# wristband_ee459.net
KiCad netlist of a schematic drawn in Altium Designer
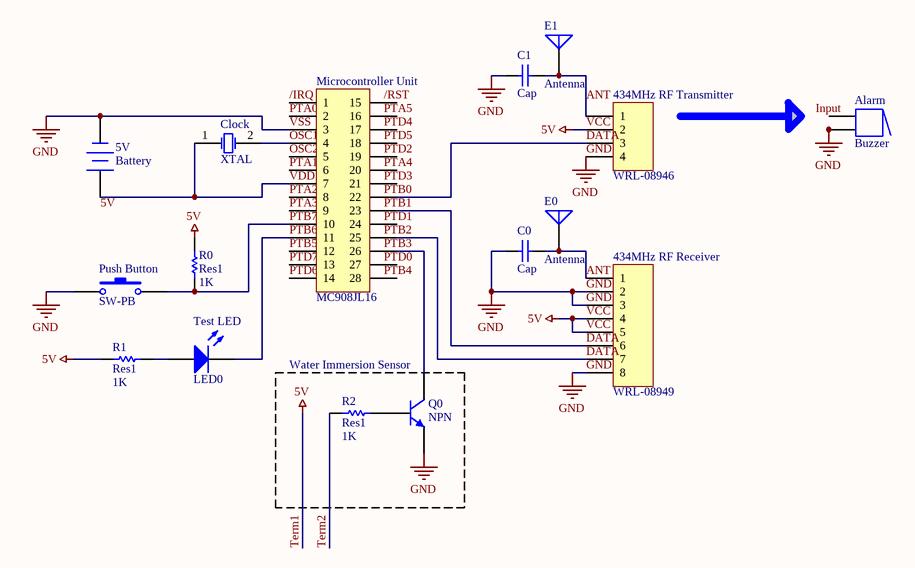
[diagram p0: wristband_ee459.SchDoc]

(export (version "E")
  (design (tool "Eeschema 10.0.6"))
  (components
    (comp (ref "5V")
      (value "Battery")
      (footprint "BAT-2")
      (description "Multicell Battery")
      (fields (field (name "PUBLISHER") "Altium Limited"))
      (libsource (lib "Miscellaneous Devices") (part "Battery"))
    )
    (comp (ref "434MHz RF Receiver")
      (value "WRL-08949")
      (footprint "HDR1X8")
      (description "Header, 8-Pin")
      (fields (field (name "PUBLISHER") "Altium Limited"))
      (libsource (lib "Miscellaneous Connectors") (part "Header 8"))
    )
    (comp (ref "434MHz RF Transmitter")
      (value "WRL-08946")
      (footprint "HDR1X4")
      (description "Header, 4-Pin")
      (fields (field (name "PUBLISHER") "Altium Limited"))
      (libsource (lib "Miscellaneous Connectors") (part "Header 4"))
    )
    (comp (ref "Alarm")
      (value "Buzzer")
      (footprint "ABSM-1574")
      (description "Magnetic Transducer Buzzer")
      (fields (field (name "PUBLISHER") "Altium Limited"))
      (libsource (lib "Miscellaneous Devices") (part "Buzzer"))
    )
    (comp (ref "C0")
      (value "Cap")
      (footprint "RAD-0.3")
      (description "Capacitor")
      (fields (field (name "PUBLISHER") "Altium Limited"))
      (libsource (lib "Miscellaneous Devices") (part "Cap"))
    )
    (comp (ref "C1")
      (value "Cap")
      (footprint "RAD-0.3")
      (description "Capacitor")
      (fields (field (name "PUBLISHER") "Altium Limited"))
      (libsource (lib "Miscellaneous Devices") (part "Cap"))
    )
    (comp (ref "Clock")
      (value "XTAL")
      (footprint "R38")
      (description "Crystal Oscillator")
      (fields (field (name "PUBLISHER") "Altium Limited"))
      (libsource (lib "Miscellaneous Devices") (part "XTAL"))
    )
    (comp (ref "E0")
      (value "Antenna")
      (footprint "PIN1")
      (description "Generic Antenna")
      (fields (field (name "PUBLISHER") "Altium Limited"))
      (libsource (lib "Miscellaneous Devices") (part "Antenna"))
    )
    (comp (ref "E1")
      (value "Antenna")
      (footprint "PIN1")
      (description "Generic Antenna")
      (fields (field (name "PUBLISHER") "Altium Limited"))
      (libsource (lib "Miscellaneous Devices") (part "Antenna"))
    )
    (comp (ref "Microcontroller Unit")
      (value "MC908JL16")
      (footprint "HDR2X14_CEN")
      (description "Header, 14-Pin, Dual row")
      (fields (field (name "PUBLISHER") "Altium Limited"))
      (libsource (lib "Miscellaneous Connectors") (part "Header 14X2A"))
    )
    (comp (ref "Push Button")
      (value "SW-PB")
      (footprint "SPST-2")
      (description "Switch")
      (fields (field (name "PUBLISHER") "Altium Limited"))
      (libsource (lib "Miscellaneous Devices") (part "SW-PB"))
    )
    (comp (ref "Q0")
      (value "NPN")
      (footprint "TO-226")
      (description "NPN Bipolar Transistor")
      (fields (field (name "PUBLISHER") "Altium Limited"))
      (libsource (lib "Miscellaneous Devices") (part "NPN"))
    )
    (comp (ref "R0")
      (value "Res1")
      (footprint "AXIAL-0.3")
      (description "Resistor")
      (fields (field (name "ALTIUM_VALUE") "1K") (field (name "PUBLISHER") "Altium Limited"))
      (libsource (lib "Miscellaneous Devices") (part "Res1"))
    )
    (comp (ref "R1")
      (value "Res1")
      (footprint "AXIAL-0.3")
      (description "Resistor")
      (fields (field (name "ALTIUM_VALUE") "1K") (field (name "PUBLISHER") "Altium Limited"))
      (libsource (lib "Miscellaneous Devices") (part "Res1"))
    )
    (comp (ref "R2")
      (value "Res1")
      (footprint "AXIAL-0.3")
      (description "Resistor")
      (fields (field (name "ALTIUM_VALUE") "1K") (field (name "PUBLISHER") "Altium Limited"))
      (libsource (lib "Miscellaneous Devices") (part "Res1"))
    )
    (comp (ref "Test LED")
      (value "LED0")
      (footprint "LED-0")
      (description "Typical INFRARED GaAs LED")
      (fields (field (name "PUBLISHER") "Altium Limited"))
      (libsource (lib "Miscellaneous Devices") (part "LED0"))
    )
  )
  (nets
    (net (code "1") (name "/ANT") (class "Default")
      (node (ref "434MHz RF Receiver") (pin "1") (pinfunction "1_1") (pintype "passive"))
      (node (ref "434MHz RF Transmitter") (pin "1") (pinfunction "1_1") (pintype "passive"))
      (node (ref "C0") (pin "2") (pinfunction "2_2") (pintype "passive"))
      (node (ref "C1") (pin "2") (pinfunction "2_2") (pintype "passive"))
      (node (ref "E0") (pin "1") (pinfunction "A_1") (pintype "passive"))
      (node (ref "E1") (pin "1") (pinfunction "A_1") (pintype "passive"))
    )
    (net (code "2") (name "/DATA") (class "Default")
      (node (ref "434MHz RF Receiver") (pin "6") (pinfunction "6_6") (pintype "passive"))
      (node (ref "434MHz RF Receiver") (pin "7") (pinfunction "7_7") (pintype "passive"))
      (node (ref "434MHz RF Transmitter") (pin "3") (pinfunction "3_3") (pintype "passive"))
      (node (ref "Microcontroller Unit") (pin "22") (pinfunction "22_22") (pintype "passive"))
      (node (ref "Microcontroller Unit") (pin "23") (pinfunction "23_23") (pintype "passive"))
      (node (ref "Microcontroller Unit") (pin "25") (pinfunction "25_25") (pintype "passive"))
    )
    (net (code "4") (name "/OSC1") (class "Default")
      (node (ref "Clock") (pin "2") (pinfunction "OSC2_2") (pintype "passive"))
      (node (ref "Microcontroller Unit") (pin "4") (pinfunction "4_4") (pintype "passive"))
    )
    (net (code "5") (name "/OSC2") (class "Default")
      (node (ref "Microcontroller Unit") (pin "5") (pinfunction "5_5") (pintype "passive"))
    )
    (net (code "6") (name "/PTA0") (class "Default")
      (node (ref "Microcontroller Unit") (pin "2") (pinfunction "2_2") (pintype "passive"))
    )
    (net (code "7") (name "/PTA1") (class "Default")
      (node (ref "Microcontroller Unit") (pin "6") (pinfunction "6_6") (pintype "passive"))
    )
    (net (code "8") (name "/PTA2") (class "Default")
      (node (ref "Microcontroller Unit") (pin "8") (pinfunction "8_8") (pintype "passive"))
    )
    (net (code "9") (name "/PTA3") (class "Default")
      (node (ref "Microcontroller Unit") (pin "9") (pinfunction "9_9") (pintype "passive"))
    )
    (net (code "17") (name "/PTB5") (class "Default")
      (node (ref "Microcontroller Unit") (pin "12") (pinfunction "12_12") (pintype "passive"))
    )
    (net (code "18") (name "/PTB6") (class "Default")
      (node (ref "Microcontroller Unit") (pin "11") (pinfunction "11_11") (pintype "passive"))
      (node (ref "Test LED") (pin "2") (pinfunction "K_2") (pintype "passive"))
    )
    (net (code "19") (name "/PTB7") (class "Default")
      (node (ref "Microcontroller Unit") (pin "10") (pinfunction "10_10") (pintype "passive"))
      (node (ref "Push Button") (pin "2") (pinfunction "2_2") (pintype "passive"))
      (node (ref "R0") (pin "1") (pinfunction "1_1") (pintype "passive"))
    )
    (net (code "26") (name "/PTD6") (class "Default")
      (node (ref "Microcontroller Unit") (pin "14") (pinfunction "14_14") (pintype "passive"))
    )
    (net (code "27") (name "/PTD7") (class "Default")
      (node (ref "Microcontroller Unit") (pin "13") (pinfunction "13_13") (pintype "passive"))
    )
    (net (code "28") (name "/Term2") (class "Default")
      (node (ref "R2") (pin "1") (pinfunction "1_1") (pintype "passive"))
    )
    (net (code "29") (name "/VDD") (class "Default")
      (node (ref "5V") (pin "1") (pinfunction "+_1") (pintype "passive"))
      (node (ref "Clock") (pin "1") (pinfunction "OSC1_1") (pintype "passive"))
      (node (ref "Microcontroller Unit") (pin "7") (pinfunction "7_7") (pintype "passive"))
    )
    (net (code "30") (name "/{slash}IRQ") (class "Default")
      (node (ref "Microcontroller Unit") (pin "1") (pinfunction "1_1") (pintype "passive"))
    )
    (net (code "32") (name "5V") (class "Default")
      (node (ref "434MHz RF Receiver") (pin "4") (pinfunction "4_4") (pintype "passive"))
      (node (ref "434MHz RF Receiver") (pin "5") (pinfunction "5_5") (pintype "passive"))
      (node (ref "434MHz RF Transmitter") (pin "2") (pinfunction "2_2") (pintype "passive"))
      (node (ref "R0") (pin "2") (pinfunction "2_2") (pintype "passive"))
      (node (ref "R1") (pin "2") (pinfunction "2_2") (pintype "passive"))
    )
    (net (code "33") (name "GND") (class "Default")
      (node (ref "434MHz RF Receiver") (pin "2") (pinfunction "2_2") (pintype "passive"))
      (node (ref "434MHz RF Receiver") (pin "3") (pinfunction "3_3") (pintype "passive"))
      (node (ref "434MHz RF Receiver") (pin "8") (pinfunction "8_8") (pintype "passive"))
      (node (ref "434MHz RF Transmitter") (pin "4") (pinfunction "4_4") (pintype "passive"))
      (node (ref "5V") (pin "2") (pinfunction "-_2") (pintype "passive"))
      (node (ref "Alarm") (pin "2") (pinfunction "2_2") (pintype "passive"))
      (node (ref "Alarm") (pin "2A") (pinfunction "2A_2A") (pintype "passive"))
      (node (ref "C0") (pin "1") (pinfunction "1_1") (pintype "passive"))
      (node (ref "C1") (pin "1") (pinfunction "1_1") (pintype "passive"))
      (node (ref "Microcontroller Unit") (pin "3") (pinfunction "3_3") (pintype "passive"))
      (node (ref "Push Button") (pin "1") (pinfunction "1_1") (pintype "passive"))
      (node (ref "Q0") (pin "3") (pinfunction "E_3") (pintype "passive"))
    )
    (net (code "34") (name "Net-(Alarm-Pad1)") (class "Default")
      (node (ref "Alarm") (pin "1") (pinfunction "1_1") (pintype "passive"))
      (node (ref "Alarm") (pin "1A") (pinfunction "1A_1A") (pintype "passive"))
    )
    (net (code "35") (name "Net-(Q0-B)") (class "Default")
      (node (ref "Q0") (pin "2") (pinfunction "B_2") (pintype "passive"))
      (node (ref "R2") (pin "2") (pinfunction "2_2") (pintype "passive"))
    )
    (net (code "36") (name "Net-(Q0-C)") (class "Default")
      (node (ref "Microcontroller Unit") (pin "26") (pinfunction "26_26") (pintype "passive"))
      (node (ref "Q0") (pin "1") (pinfunction "C_1") (pintype "passive"))
    )
    (net (code "37") (name "Net-(Test LED-A)") (class "Default")
      (node (ref "R1") (pin "1") (pinfunction "1_1") (pintype "passive"))
      (node (ref "Test LED") (pin "1") (pinfunction "A_1") (pintype "passive"))
    )
    (net (code "38") (name "unconnected-(Microcontroller Unit-Pad15)") (class "Default")
      (node (ref "Microcontroller Unit") (pin "15") (pinfunction "15_15") (pintype "passive"))
    )
    (net (code "39") (name "unconnected-(Microcontroller Unit-Pad16)") (class "Default")
      (node (ref "Microcontroller Unit") (pin "16") (pinfunction "16_16") (pintype "passive"))
    )
    (net (code "40") (name "unconnected-(Microcontroller Unit-Pad17)") (class "Default")
      (node (ref "Microcontroller Unit") (pin "17") (pinfunction "17_17") (pintype "passive"))
    )
    (net (code "41") (name "unconnected-(Microcontroller Unit-Pad18)") (class "Default")
      (node (ref "Microcontroller Unit") (pin "18") (pinfunction "18_18") (pintype "passive"))
    )
    (net (code "42") (name "unconnected-(Microcontroller Unit-Pad19)") (class "Default")
      (node (ref "Microcontroller Unit") (pin "19") (pinfunction "19_19") (pintype "passive"))
    )
    (net (code "43") (name "unconnected-(Microcontroller Unit-Pad20)") (class "Default")
      (node (ref "Microcontroller Unit") (pin "20") (pinfunction "20_20") (pintype "passive"))
    )
    (net (code "44") (name "unconnected-(Microcontroller Unit-Pad21)") (class "Default")
      (node (ref "Microcontroller Unit") (pin "21") (pinfunction "21_21") (pintype "passive"))
    )
    (net (code "45") (name "unconnected-(Microcontroller Unit-Pad24)") (class "Default")
      (node (ref "Microcontroller Unit") (pin "24") (pinfunction "24_24") (pintype "passive"))
    )
    (net (code "46") (name "unconnected-(Microcontroller Unit-Pad27)") (class "Default")
      (node (ref "Microcontroller Unit") (pin "27") (pinfunction "27_27") (pintype "passive"))
    )
    (net (code "47") (name "unconnected-(Microcontroller Unit-Pad28)") (class "Default")
      (node (ref "Microcontroller Unit") (pin "28") (pinfunction "28_28") (pintype "passive"))
    )
  )
)
